# Artix7_ProgramAndConfig.net
KiCad netlist of a schematic drawn in Altium Designer
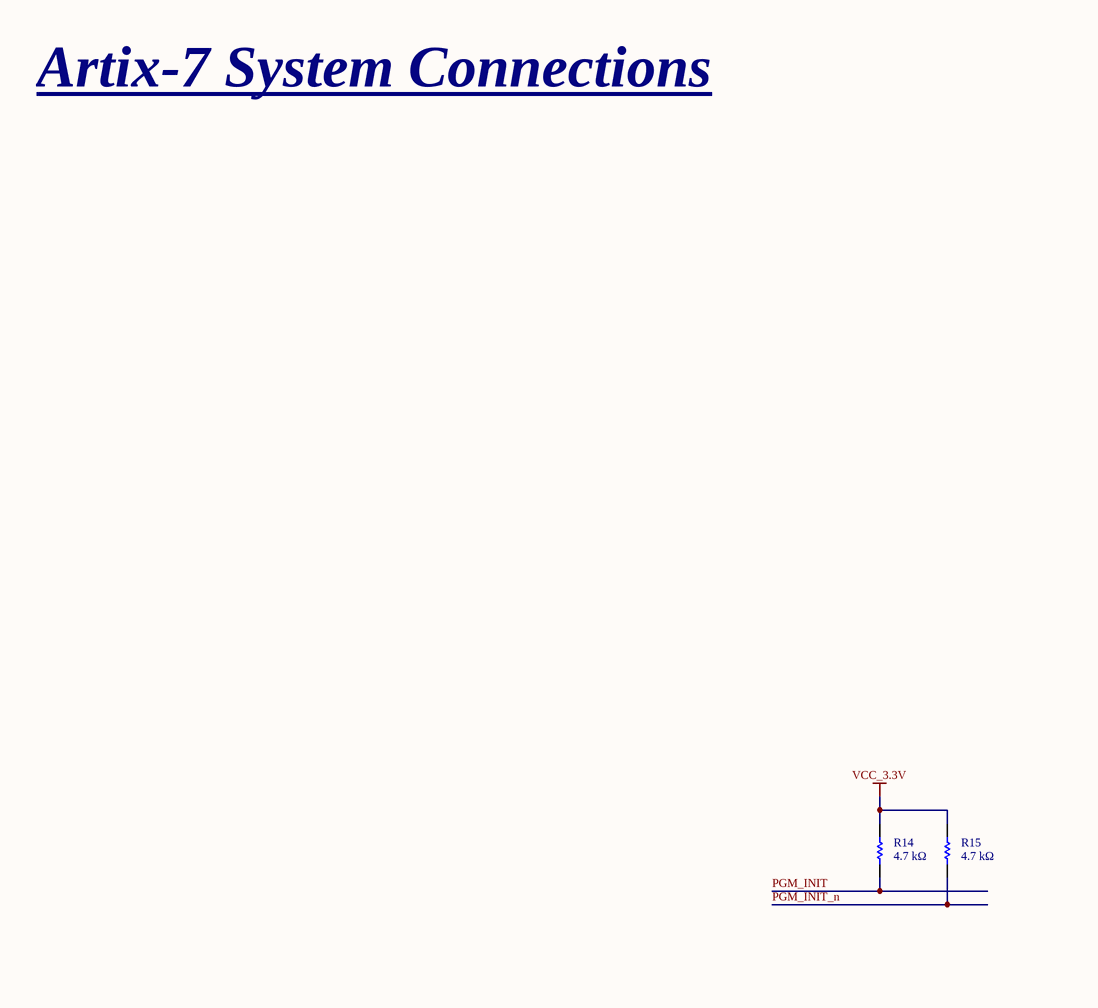
[diagram p0: Artix7_ProgramAndConfig.SchDoc, left]
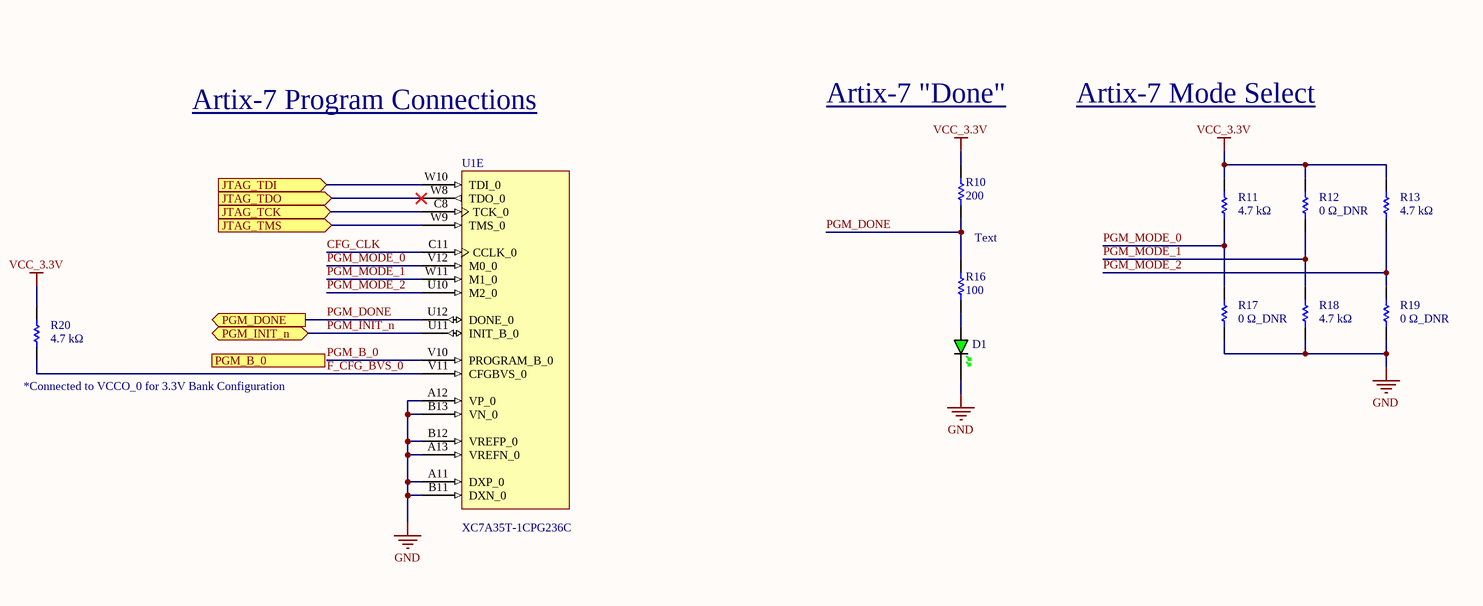
[diagram p1: Artix7_ProgramAndConfig.SchDoc, right]

(export (version "E")
  (design (tool "Eeschema 10.0.6"))
  (components
    (comp (ref "D1")
      (value "LED_0402_GREEN")
      (footprint "LED_0402_GREEN")
      (description "LED 0402 GREEN SMD")
      (libsource (lib "Personal Workspace") (part "LED_0805_GREEN"))
    )
    (comp (ref "R10")
      (value "200")
      (footprint "RESC0402(1005)_L")
      (description "Chip Resistor, 200 Ohms, +/-5 %, 63 mW, -55 to 155 degC, 0402")
      (fields (field (name "POWER") "63mW") (field (name "TOLERANCE") "5%"))
      (libsource (lib "Personal Workspace") (part "RES-2"))
    )
    (comp (ref "R11")
      (value "ERJ-3EKF4701V")
      (footprint "RESC1608X55X30LL15T15")
      (fields
        (field (name "TOLERANCE") "1%")
        (field (name "POWER") "100mW")
        (field (name "RESISTANCE") "4.7 kΩ")
      )
      (libsource (lib "Personal Workspace") (part "RES-2"))
    )
    (comp (ref "R12")
      (value "ERJ-3EKF4701V")
      (footprint "RESC1608X55X30LL15T15")
      (fields
        (field (name "TOLERANCE") "1%")
        (field (name "POWER") "100mW")
        (field (name "RESISTANCE") "0 Ω_DNR")
      )
      (libsource (lib "Personal Workspace") (part "RES-2"))
    )
    (comp (ref "R13")
      (value "ERJ-3EKF4701V")
      (footprint "RESC1608X55X30LL15T15")
      (fields
        (field (name "TOLERANCE") "1%")
        (field (name "POWER") "100mW")
        (field (name "RESISTANCE") "4.7 kΩ")
      )
      (libsource (lib "Personal Workspace") (part "RES-2"))
    )
    (comp (ref "R14")
      (value "ERJ-3EKF4701V")
      (footprint "RESC1608X55X30LL15T15")
      (fields
        (field (name "TOLERANCE") "1%")
        (field (name "POWER") "100mW")
        (field (name "RESISTANCE") "4.7 kΩ")
      )
      (libsource (lib "Personal Workspace") (part "RES-2"))
    )
    (comp (ref "R15")
      (value "ERJ-3EKF4701V")
      (footprint "RESC1608X55X30LL15T15")
      (fields
        (field (name "TOLERANCE") "1%")
        (field (name "POWER") "100mW")
        (field (name "RESISTANCE") "4.7 kΩ")
      )
      (libsource (lib "Personal Workspace") (part "RES-2"))
    )
    (comp (ref "R16")
      (value "100")
      (footprint "RESC0402(1005)_L")
      (description "Chip Resistor, 100 Ohms, +/-1 %, 63 mW, -55 to 155 degC, 0402")
      (fields (field (name "POWER") "63mW") (field (name "TOLERANCE") "1%"))
      (libsource (lib "Personal Workspace") (part "RES-2"))
    )
    (comp (ref "R17")
      (value "ERJ-3EKF4701V")
      (footprint "RESC1608X55X30LL15T15")
      (fields
        (field (name "TOLERANCE") "1%")
        (field (name "POWER") "100mW")
        (field (name "RESISTANCE") "0 Ω_DNR")
      )
      (libsource (lib "Personal Workspace") (part "RES-2"))
    )
    (comp (ref "R18")
      (value "ERJ-3EKF4701V")
      (footprint "RESC1608X55X30LL15T15")
      (fields
        (field (name "TOLERANCE") "1%")
        (field (name "POWER") "100mW")
        (field (name "RESISTANCE") "4.7 kΩ")
      )
      (libsource (lib "Personal Workspace") (part "RES-2"))
    )
    (comp (ref "R19")
      (value "ERJ-3EKF4701V")
      (footprint "RESC1608X55X30LL15T15")
      (fields
        (field (name "TOLERANCE") "1%")
        (field (name "POWER") "100mW")
        (field (name "RESISTANCE") "0 Ω_DNR")
      )
      (libsource (lib "Personal Workspace") (part "RES-2"))
    )
    (comp (ref "R20")
      (value "ERJ-3EKF4701V")
      (footprint "RESC1608X55X30LL15T15")
      (fields
        (field (name "TOLERANCE") "1%")
        (field (name "POWER") "100mW")
        (field (name "RESISTANCE") "4.7 kΩ")
      )
      (libsource (lib "Personal Workspace") (part "RES-2"))
    )
    (comp (ref "U1")
      (value "XC7A35T-1CPG236C")
      (footprint "CPG236")
      (description "Artix-7 FPGA, 106 User I/Os, 2 GTP, 238-Ball BGA, Speed Grade 1, Commercial Grade, Pb-Free")
      (fields (field (name "MANUFACTURER") "Xilinx"))
      (libsource (lib "Altium Content Vault") (part "XLNX-XC7A35T-CPG236"))
    )
  )
  (nets
    (net (code "1") (name "/CFG_CLK") (class "Default")
      (node (ref "U1") (pin "C11") (pinfunction "CCLK_0_C11") (pintype "input"))
    )
    (net (code "2") (name "/F_CFG_BVS_0") (class "Default")
      (node (ref "R20") (pin "1") (pinfunction "1_1") (pintype "passive"))
      (node (ref "U1") (pin "V11") (pinfunction "CFGBVS_0_V11") (pintype "input"))
    )
    (net (code "3") (name "/JTAG_TCK") (class "Default")
      (node (ref "U1") (pin "C8") (pinfunction "TCK_0_C8") (pintype "input"))
    )
    (net (code "4") (name "/JTAG_TDI") (class "Default")
      (node (ref "U1") (pin "W10") (pinfunction "TDI_0_W10") (pintype "input"))
    )
    (net (code "5") (name "/JTAG_TDO") (class "Default")
      (node (ref "U1") (pin "W8") (pinfunction "TDO_0_W8") (pintype "output+no_connect"))
    )
    (net (code "6") (name "/JTAG_TMS") (class "Default")
      (node (ref "U1") (pin "W9") (pinfunction "TMS_0_W9") (pintype "input"))
    )
    (net (code "7") (name "/PGM_B_0") (class "Default")
      (node (ref "U1") (pin "V10") (pinfunction "PROGRAM_B_0_V10") (pintype "input"))
    )
    (net (code "8") (name "/PGM_DONE") (class "Default")
      (node (ref "R10") (pin "1") (pinfunction "1_1") (pintype "passive"))
      (node (ref "R16") (pin "2") (pinfunction "2_2") (pintype "passive"))
      (node (ref "U1") (pin "U12") (pinfunction "DONE_0_U12") (pintype "bidirectional"))
    )
    (net (code "9") (name "/PGM_INIT") (class "Default")
      (node (ref "R14") (pin "1") (pinfunction "1_1") (pintype "passive"))
    )
    (net (code "10") (name "/PGM_INIT_n") (class "Default")
      (node (ref "R15") (pin "1") (pinfunction "1_1") (pintype "passive"))
      (node (ref "U1") (pin "U11") (pinfunction "INIT_B_0_U11") (pintype "bidirectional"))
    )
    (net (code "11") (name "/PGM_MODE_0") (class "Default")
      (node (ref "R11") (pin "1") (pinfunction "1_1") (pintype "passive"))
      (node (ref "R17") (pin "2") (pinfunction "2_2") (pintype "passive"))
      (node (ref "U1") (pin "V12") (pinfunction "M0_0_V12") (pintype "input"))
    )
    (net (code "12") (name "/PGM_MODE_1") (class "Default")
      (node (ref "R12") (pin "1") (pinfunction "1_1") (pintype "passive"))
      (node (ref "R18") (pin "2") (pinfunction "2_2") (pintype "passive"))
      (node (ref "U1") (pin "W11") (pinfunction "M1_0_W11") (pintype "input"))
    )
    (net (code "13") (name "/PGM_MODE_2") (class "Default")
      (node (ref "R13") (pin "1") (pinfunction "1_1") (pintype "passive"))
      (node (ref "R19") (pin "2") (pinfunction "2_2") (pintype "passive"))
      (node (ref "U1") (pin "U10") (pinfunction "M2_0_U10") (pintype "input"))
    )
    (net (code "14") (name "GND") (class "Default")
      (node (ref "D1") (pin "K") (pinfunction "K_K") (pintype "passive"))
      (node (ref "R17") (pin "1") (pinfunction "1_1") (pintype "passive"))
      (node (ref "R18") (pin "1") (pinfunction "1_1") (pintype "passive"))
      (node (ref "R19") (pin "1") (pinfunction "1_1") (pintype "passive"))
      (node (ref "U1") (pin "A11") (pinfunction "DXP_0_A11") (pintype "input"))
      (node (ref "U1") (pin "A12") (pinfunction "VP_0_A12") (pintype "input"))
      (node (ref "U1") (pin "A13") (pinfunction "VREFN_0_A13") (pintype "input"))
      (node (ref "U1") (pin "B11") (pinfunction "DXN_0_B11") (pintype "input"))
      (node (ref "U1") (pin "B12") (pinfunction "VREFP_0_B12") (pintype "input"))
      (node (ref "U1") (pin "B13") (pinfunction "VN_0_B13") (pintype "input"))
    )
    (net (code "15") (name "Net-(D1-PadA)") (class "Default")
      (node (ref "D1") (pin "A") (pinfunction "A_A") (pintype "passive"))
      (node (ref "R16") (pin "1") (pinfunction "1_1") (pintype "passive"))
    )
    (net (code "16") (name "VCC_3.3V") (class "Default")
      (node (ref "R10") (pin "2") (pinfunction "2_2") (pintype "passive"))
      (node (ref "R11") (pin "2") (pinfunction "2_2") (pintype "passive"))
      (node (ref "R12") (pin "2") (pinfunction "2_2") (pintype "passive"))
      (node (ref "R13") (pin "2") (pinfunction "2_2") (pintype "passive"))
      (node (ref "R14") (pin "2") (pinfunction "2_2") (pintype "passive"))
      (node (ref "R15") (pin "2") (pinfunction "2_2") (pintype "passive"))
      (node (ref "R20") (pin "2") (pinfunction "2_2") (pintype "passive"))
    )
  )
)
